# LED.net
KiCad netlist of a schematic drawn in Altium Designer
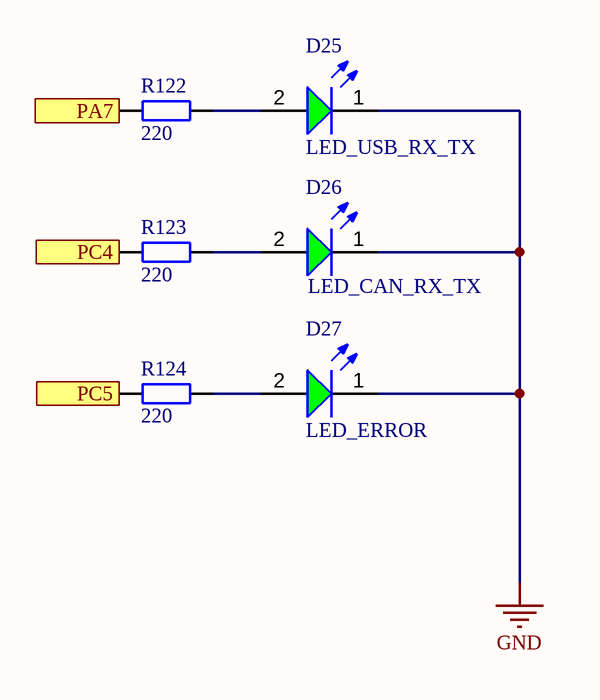
[diagram p0: LED.SchDoc]

(export (version "E")
  (design (tool "Eeschema 10.0.6"))
  (components
    (comp (ref "D25")
      (value "LED_USB_RX_TX")
      (footprint "WL-SMCW_0603_150060xx75000")
      (description "430mcd Colorless transparence 520nm Emerald 140° LED0603 Light Emitting Diodes (LED) ROHS")
      (libsource (lib "AUSB") (part "CMP-1426-00002-4"))
    )
    (comp (ref "D26")
      (value "LED_CAN_RX_TX")
      (footprint "WL-SMCW_0603_150060xx75000")
      (description "430mcd Colorless transparence 520nm Emerald 140° LED0603 Light Emitting Diodes (LED) ROHS")
      (libsource (lib "AUSB") (part "CMP-1426-00002-4"))
    )
    (comp (ref "D27")
      (value "LED_ERROR")
      (footprint "WL-SMCW_0603_150060xx75000")
      (description "430mcd Colorless transparence 520nm Emerald 140° LED0603 Light Emitting Diodes (LED) ROHS")
      (libsource (lib "AUSB") (part "CMP-1426-00002-4"))
    )
    (comp (ref "R122")
      (value "220")
      (footprint "tro smd 0603")
      (description "RES")
      (libsource (lib "AUSB") (part "Tro 0603 1% 10k"))
    )
    (comp (ref "R123")
      (value "220")
      (footprint "tro smd 0603")
      (description "RES")
      (libsource (lib "AUSB") (part "Tro 0603 1% 10k"))
    )
    (comp (ref "R124")
      (value "220")
      (footprint "tro smd 0603")
      (description "RES")
      (libsource (lib "AUSB") (part "Tro 0603 1% 10k"))
    )
  )
  (nets
    (net (code "1") (name "/PA7") (class "Default")
      (node (ref "R122") (pin "1") (pinfunction "1_1") (pintype "passive"))
    )
    (net (code "2") (name "/PC4") (class "Default")
      (node (ref "R123") (pin "1") (pinfunction "1_1") (pintype "passive"))
    )
    (net (code "3") (name "/PC5") (class "Default")
      (node (ref "R124") (pin "1") (pinfunction "1_1") (pintype "passive"))
    )
    (net (code "4") (name "GND") (class "Default")
      (node (ref "D25") (pin "1") (pinfunction "K_1") (pintype "passive"))
      (node (ref "D26") (pin "1") (pinfunction "K_1") (pintype "passive"))
      (node (ref "D27") (pin "1") (pinfunction "K_1") (pintype "passive"))
    )
    (net (code "5") (name "Net-(D25-A)") (class "Default")
      (node (ref "D25") (pin "2") (pinfunction "A_2") (pintype "passive"))
      (node (ref "R122") (pin "2") (pinfunction "2_2") (pintype "passive"))
    )
    (net (code "6") (name "Net-(D26-A)") (class "Default")
      (node (ref "D26") (pin "2") (pinfunction "A_2") (pintype "passive"))
      (node (ref "R123") (pin "2") (pinfunction "2_2") (pintype "passive"))
    )
    (net (code "7") (name "Net-(D27-A)") (class "Default")
      (node (ref "D27") (pin "2") (pinfunction "A_2") (pintype "passive"))
      (node (ref "R124") (pin "2") (pinfunction "2_2") (pintype "passive"))
    )
  )
)
